# power.net
KiCad netlist of a schematic drawn in Altium Designer
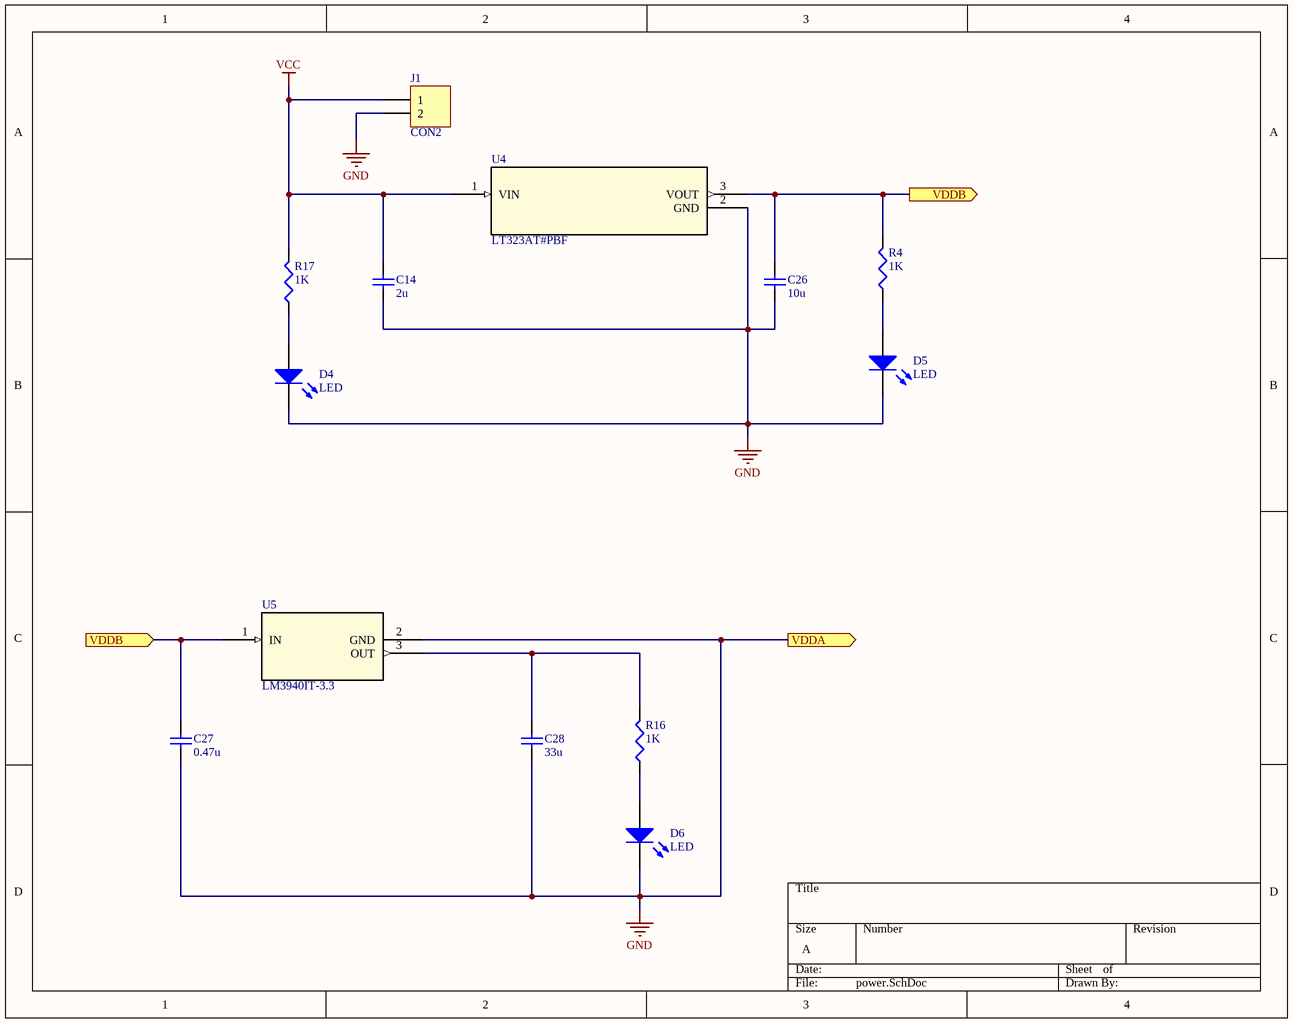
[diagram p0: power.SchDoc]

(export (version "E")
  (design (tool "Eeschema 10.0.6"))
  (components
    (comp (ref "C14")
      (value "2u")
      (footprint "C1206")
      (description "Capacitor (Semiconductor SIM Model)")
      (fields (field (name "PUBLISHER") "Altium Limited"))
      (libsource (lib "Miscellaneous Devices") (part "Cap Semi"))
    )
    (comp (ref "C26")
      (value "10u")
      (footprint "C1206")
      (description "Capacitor (Semiconductor SIM Model)")
      (fields (field (name "PUBLISHER") "Altium Limited"))
      (libsource (lib "Miscellaneous Devices") (part "Cap Semi"))
    )
    (comp (ref "C27")
      (value "0.47u")
      (footprint "C1206")
      (description "Capacitor (Semiconductor SIM Model)")
      (fields (field (name "PUBLISHER") "Altium Limited"))
      (libsource (lib "Miscellaneous Devices") (part "Cap Semi"))
    )
    (comp (ref "C28")
      (value "33u")
      (footprint "C1206")
      (description "Capacitor (Semiconductor SIM Model)")
      (fields (field (name "PUBLISHER") "Altium Limited"))
      (libsource (lib "Miscellaneous Devices") (part "Cap Semi"))
    )
    (comp (ref "D4")
      (value "LED")
      (footprint "3.2X1.6X1.1")
      (description "Typical RED, GREEN, YELLOW, AMBER GaAs LED")
      (fields (field (name "PUBLISHER") "Altium Limited"))
      (libsource (lib "Miscellaneous Devices") (part "LED2"))
    )
    (comp (ref "D5")
      (value "LED")
      (footprint "3.2X1.6X1.1")
      (description "Typical RED, GREEN, YELLOW, AMBER GaAs LED")
      (fields (field (name "PUBLISHER") "Altium Limited"))
      (libsource (lib "Miscellaneous Devices") (part "LED2"))
    )
    (comp (ref "D6")
      (value "LED")
      (footprint "3.2X1.6X1.1")
      (description "Typical RED, GREEN, YELLOW, AMBER GaAs LED")
      (fields (field (name "PUBLISHER") "Altium Limited"))
      (libsource (lib "Miscellaneous Devices") (part "LED2"))
    )
    (comp (ref "J1")
      (value "CON2")
      (footprint "HDR1X2")
      (description "Header, 2-Pin")
      (fields (field (name "PUBLISHER") "Altium Limited"))
      (libsource (lib "Miscellaneous Connectors") (part "Header 2"))
    )
    (comp (ref "R4")
      (value "1K")
      (footprint "J1-0603")
      (fields (field (name "PUBLISHER") "Altium Limited"))
      (libsource (lib "Miscellaneous Devices") (part "Res3"))
    )
    (comp (ref "R16")
      (value "1K")
      (footprint "J1-0603")
      (fields (field (name "PUBLISHER") "Altium Limited"))
      (libsource (lib "Miscellaneous Devices") (part "Res3"))
    )
    (comp (ref "R17")
      (value "1K")
      (footprint "J1-0603")
      (fields (field (name "PUBLISHER") "Altium Limited"))
      (libsource (lib "Miscellaneous Devices") (part "Res3"))
    )
    (comp (ref "U4")
      (value "LT323AT#PBF")
      (footprint "TO220-3_T_LIT")
      (description "No Description Available")
      (fields (field (name "COPYRIGHT") "Copyright (C) 2022 Ultra Librarian. All rights reserved."))
      (libsource (lib "LT323AT&hash_PBF") (part "LT323AT#PBF"))
    )
    (comp (ref "U5")
      (value "LM3940IT-3.3")
      (footprint "T03B")
      (description "No Description Available")
      (fields (field (name "COPYRIGHT") "Copyright (C) 2022 Ultra Librarian. All rights reserved."))
      (libsource (lib "LM3940IT-3P3") (part "LM3940IT-3.3"))
    )
  )
  (nets
    (net (code "1") (name "/VDDB") (class "Default")
      (node (ref "C26") (pin "2") (pinfunction "2_2") (pintype "passive"))
      (node (ref "C27") (pin "2") (pinfunction "2_2") (pintype "passive"))
      (node (ref "R4") (pin "2") (pinfunction "2_2") (pintype "passive"))
      (node (ref "U4") (pin "3") (pinfunction "VOUT_3") (pintype "output"))
      (node (ref "U5") (pin "1") (pinfunction "IN_1") (pintype "input"))
    )
    (net (code "2") (name "GND") (class "Default")
      (node (ref "C14") (pin "1") (pinfunction "1_1") (pintype "passive"))
      (node (ref "C26") (pin "1") (pinfunction "1_1") (pintype "passive"))
      (node (ref "C27") (pin "1") (pinfunction "1_1") (pintype "passive"))
      (node (ref "C28") (pin "1") (pinfunction "1_1") (pintype "passive"))
      (node (ref "D4") (pin "2") (pinfunction "K_2") (pintype "passive"))
      (node (ref "D5") (pin "2") (pinfunction "K_2") (pintype "passive"))
      (node (ref "D6") (pin "2") (pinfunction "K_2") (pintype "passive"))
      (node (ref "J1") (pin "2") (pinfunction "2_2") (pintype "passive"))
      (node (ref "U4") (pin "2") (pinfunction "GND_2") (pintype "power_in"))
      (node (ref "U5") (pin "2") (pinfunction "GND_2") (pintype "passive"))
    )
    (net (code "3") (name "Net-(D4-A)") (class "Default")
      (node (ref "D4") (pin "1") (pinfunction "A_1") (pintype "passive"))
      (node (ref "R17") (pin "1") (pinfunction "1_1") (pintype "passive"))
    )
    (net (code "4") (name "Net-(D5-A)") (class "Default")
      (node (ref "D5") (pin "1") (pinfunction "A_1") (pintype "passive"))
      (node (ref "R4") (pin "1") (pinfunction "1_1") (pintype "passive"))
    )
    (net (code "5") (name "Net-(D6-A)") (class "Default")
      (node (ref "D6") (pin "1") (pinfunction "A_1") (pintype "passive"))
      (node (ref "R16") (pin "1") (pinfunction "1_1") (pintype "passive"))
    )
    (net (code "6") (name "Net-(U5-OUT)") (class "Default")
      (node (ref "C28") (pin "2") (pinfunction "2_2") (pintype "passive"))
      (node (ref "R16") (pin "2") (pinfunction "2_2") (pintype "passive"))
      (node (ref "U5") (pin "3") (pinfunction "OUT_3") (pintype "output"))
    )
    (net (code "7") (name "VCC") (class "Default")
      (node (ref "C14") (pin "2") (pinfunction "2_2") (pintype "passive"))
      (node (ref "J1") (pin "1") (pinfunction "1_1") (pintype "passive"))
      (node (ref "R17") (pin "2") (pinfunction "2_2") (pintype "passive"))
      (node (ref "U4") (pin "1") (pinfunction "VIN_1") (pintype "input"))
    )
  )
)
